# MMIrLedEm.net
KiCad netlist of a schematic drawn in EAGLE
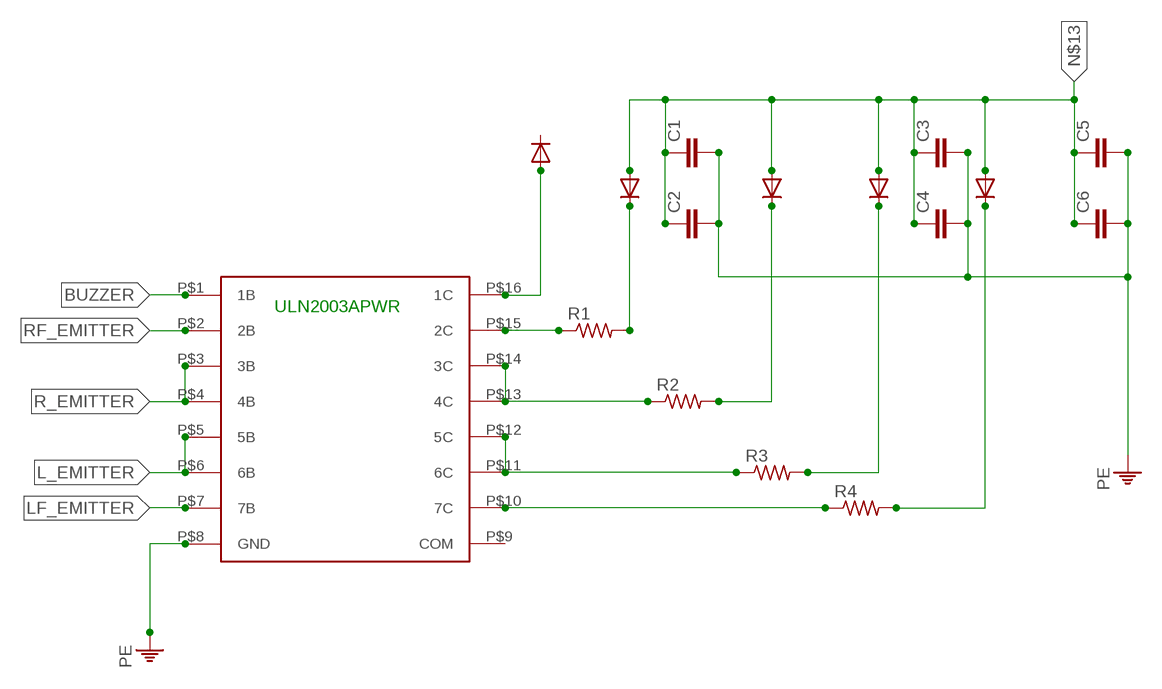
[diagram p0: schematic, sheet 1]

(export (version "E")
  (design (tool "Eeschema 10.0.6"))
  (components
    (comp (ref "C1")
      (value "C-EUC1206")
      (footprint "eagle-import:C1206")
      (libsource (lib "eagle-import") (part "C-EUC1206"))
    )
    (comp (ref "C2")
      (value "C-EUC1206")
      (footprint "eagle-import:C1206")
      (libsource (lib "eagle-import") (part "C-EUC1206"))
    )
    (comp (ref "C3")
      (value "C-EUC1206")
      (footprint "eagle-import:C1206")
      (libsource (lib "eagle-import") (part "C-EUC1206"))
    )
    (comp (ref "C4")
      (value "C-EUC1206")
      (footprint "eagle-import:C1206")
      (libsource (lib "eagle-import") (part "C-EUC1206"))
    )
    (comp (ref "C5")
      (value "C-EUC1206")
      (footprint "eagle-import:C1206")
      (libsource (lib "eagle-import") (part "C-EUC1206"))
    )
    (comp (ref "C6")
      (value "C-EUC1206")
      (footprint "eagle-import:C1206")
      (libsource (lib "eagle-import") (part "C-EUC1206"))
    )
    (comp (ref "R1")
      (value "R-US_R1206")
      (footprint "eagle-import:R1206")
      (libsource (lib "eagle-import") (part "R-US_R1206"))
    )
    (comp (ref "R2")
      (value "R-US_R1206")
      (footprint "eagle-import:R1206")
      (libsource (lib "eagle-import") (part "R-US_R1206"))
    )
    (comp (ref "R3")
      (value "R-US_R1206")
      (footprint "eagle-import:R1206")
      (libsource (lib "eagle-import") (part "R-US_R1206"))
    )
    (comp (ref "R4")
      (value "R-US_R1206")
      (footprint "eagle-import:R1206")
      (libsource (lib "eagle-import") (part "R-US_R1206"))
    )
    (comp (ref "U$1")
      (value "ULN")
      (footprint "eagle-import:ULN")
      (libsource (lib "eagle-import") (part "ULN"))
    )
  )
  (nets
    (net (code "1") (name "BUZZER") (class "Default")
      (node (ref "U$1") (pin "P$1") (pinfunction "1B_P$1") (pintype "bidirectional"))
    )
    (net (code "2") (name "LF_EMITTER") (class "Default")
      (node (ref "U$1") (pin "P$7") (pinfunction "7B_P$7") (pintype "bidirectional"))
    )
    (net (code "3") (name "L_EMITTER") (class "Default")
      (node (ref "U$1") (pin "P$5") (pinfunction "5B_P$5") (pintype "bidirectional"))
      (node (ref "U$1") (pin "P$6") (pinfunction "6B_P$6") (pintype "bidirectional"))
    )
    (net (code "4") (name "N$13") (class "Default")
      (node (ref "C1") (pin "1") (pinfunction "1_1") (pintype "passive"))
      (node (ref "C2") (pin "1") (pinfunction "1_1") (pintype "passive"))
      (node (ref "C3") (pin "1") (pinfunction "1_1") (pintype "passive"))
      (node (ref "C4") (pin "1") (pinfunction "1_1") (pintype "passive"))
      (node (ref "C5") (pin "1") (pinfunction "1_1") (pintype "passive"))
      (node (ref "C6") (pin "1") (pinfunction "1_1") (pintype "passive"))
    )
    (net (code "5") (name "Net-(U$1-2C)") (class "Default")
      (node (ref "R1") (pin "1") (pinfunction "1_1") (pintype "passive"))
      (node (ref "U$1") (pin "P$15") (pinfunction "2C_P$15") (pintype "bidirectional"))
    )
    (net (code "6") (name "Net-(U$1-3C)") (class "Default")
      (node (ref "R2") (pin "1") (pinfunction "1_1") (pintype "passive"))
      (node (ref "U$1") (pin "P$13") (pinfunction "4C_P$13") (pintype "bidirectional"))
      (node (ref "U$1") (pin "P$14") (pinfunction "3C_P$14") (pintype "bidirectional"))
    )
    (net (code "7") (name "Net-(U$1-5C)") (class "Default")
      (node (ref "R3") (pin "1") (pinfunction "1_1") (pintype "passive"))
      (node (ref "U$1") (pin "P$11") (pinfunction "6C_P$11") (pintype "bidirectional"))
      (node (ref "U$1") (pin "P$12") (pinfunction "5C_P$12") (pintype "bidirectional"))
    )
    (net (code "8") (name "Net-(U$1-7C)") (class "Default")
      (node (ref "R4") (pin "1") (pinfunction "1_1") (pintype "passive"))
      (node (ref "U$1") (pin "P$10") (pinfunction "7C_P$10") (pintype "bidirectional"))
    )
    (net (code "9") (name "PE") (class "Default")
      (node (ref "C1") (pin "2") (pinfunction "2_2") (pintype "passive"))
      (node (ref "C2") (pin "2") (pinfunction "2_2") (pintype "passive"))
      (node (ref "C3") (pin "2") (pinfunction "2_2") (pintype "passive"))
      (node (ref "C4") (pin "2") (pinfunction "2_2") (pintype "passive"))
      (node (ref "C5") (pin "2") (pinfunction "2_2") (pintype "passive"))
      (node (ref "C6") (pin "2") (pinfunction "2_2") (pintype "passive"))
      (node (ref "U$1") (pin "P$8") (pinfunction "GND_P$8") (pintype "bidirectional"))
    )
    (net (code "10") (name "RF_EMITTER") (class "Default")
      (node (ref "U$1") (pin "P$2") (pinfunction "2B_P$2") (pintype "bidirectional"))
    )
    (net (code "11") (name "R_EMITTER") (class "Default")
      (node (ref "U$1") (pin "P$3") (pinfunction "3B_P$3") (pintype "bidirectional"))
      (node (ref "U$1") (pin "P$4") (pinfunction "4B_P$4") (pintype "bidirectional"))
    )
    (net (code "12") (name "unconnected-(R1-Pad2)") (class "Default")
      (node (ref "R1") (pin "2") (pinfunction "2_2") (pintype "passive"))
    )
    (net (code "13") (name "unconnected-(R2-Pad2)") (class "Default")
      (node (ref "R2") (pin "2") (pinfunction "2_2") (pintype "passive"))
    )
    (net (code "14") (name "unconnected-(R3-Pad2)") (class "Default")
      (node (ref "R3") (pin "2") (pinfunction "2_2") (pintype "passive"))
    )
    (net (code "15") (name "unconnected-(R4-Pad2)") (class "Default")
      (node (ref "R4") (pin "2") (pinfunction "2_2") (pintype "passive"))
    )
    (net (code "16") (name "unconnected-(U$1-1C-PadP$16)") (class "Default")
      (node (ref "U$1") (pin "P$16") (pinfunction "1C_P$16") (pintype "bidirectional"))
    )
    (net (code "17") (name "unconnected-(U$1-COM-PadP$9)") (class "Default")
      (node (ref "U$1") (pin "P$9") (pinfunction "COM_P$9") (pintype "bidirectional"))
    )
  )
)
